# emojipad_v2.net
KiCad netlist of a schematic drawn in EAGLE
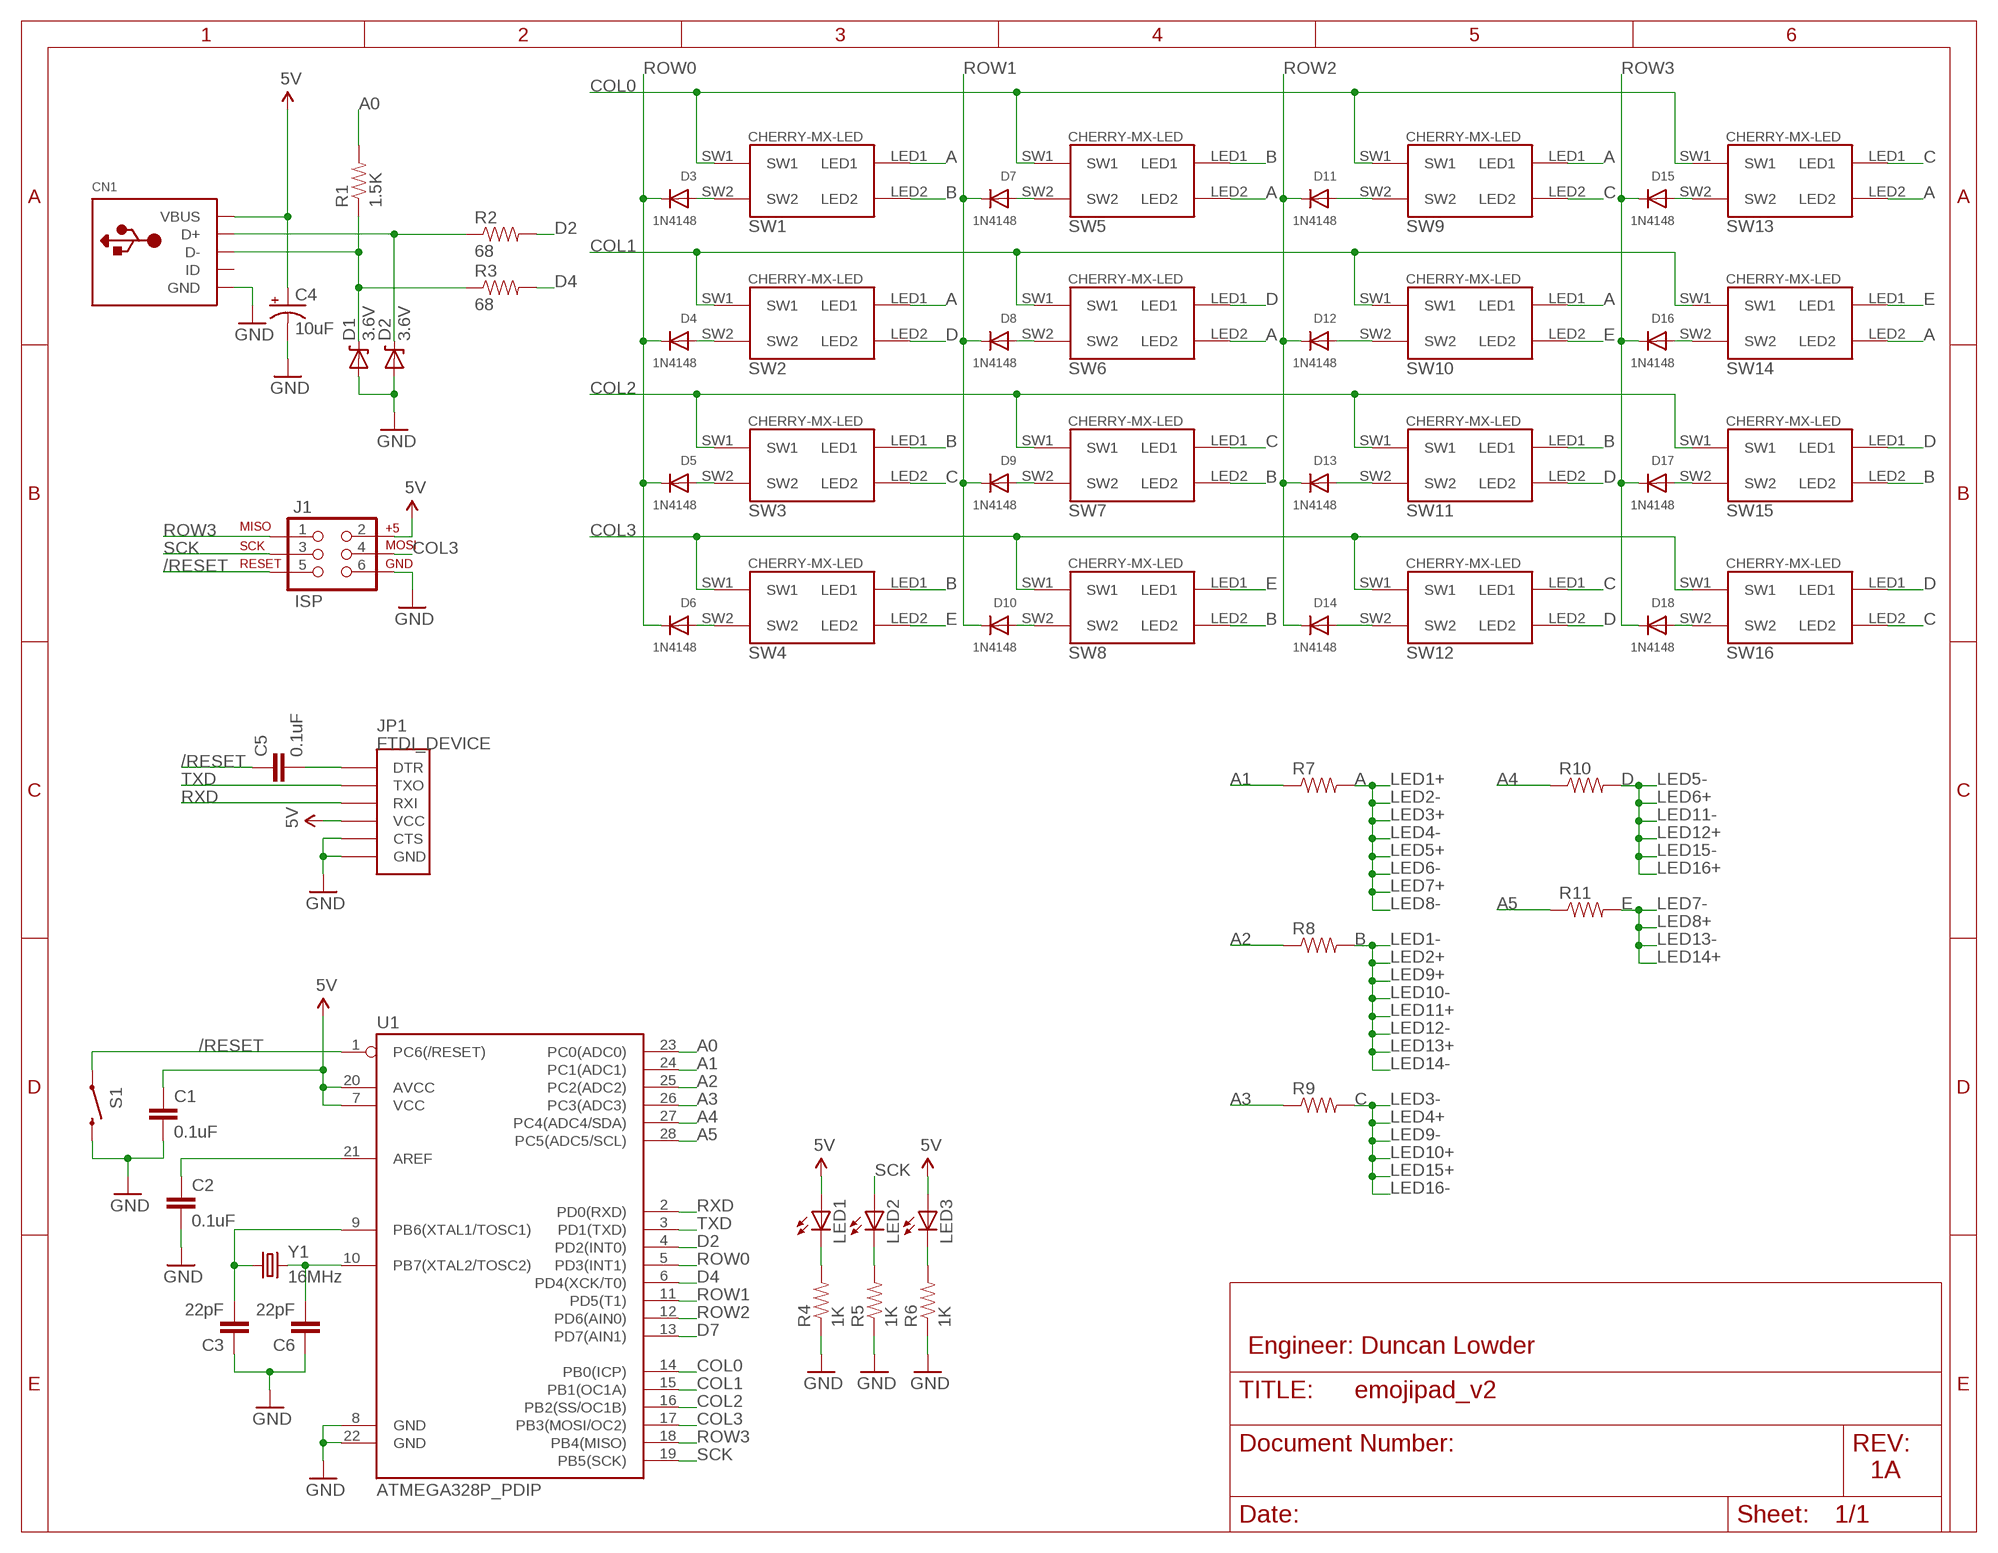
[diagram p0: schematic, sheet 1]

(export (version "E")
  (design (tool "Eeschema 10.0.6"))
  (components
    (comp (ref "C1")
      (value "0.1uF")
      (footprint "eagle-import:CAP-PTH-SMALL")
      (libsource (lib "eagle-import") (part "CAPPTH"))
    )
    (comp (ref "C2")
      (value "0.1uF")
      (footprint "eagle-import:CAP-PTH-SMALL")
      (libsource (lib "eagle-import") (part "CAPPTH"))
    )
    (comp (ref "C3")
      (value "22pF")
      (footprint "eagle-import:CAP-PTH-SMALL")
      (libsource (lib "eagle-import") (part "CAPPTH"))
    )
    (comp (ref "C4")
      (value "10uF")
      (footprint "eagle-import:CPOL-RADIAL-10UF-25V")
      (libsource (lib "eagle-import") (part "CAP_POLPTH2"))
    )
    (comp (ref "C5")
      (value "0.1uF")
      (footprint "eagle-import:CAP-PTH-SMALL")
      (libsource (lib "eagle-import") (part "SparkFun-Passives_CAPPTH"))
    )
    (comp (ref "C6")
      (value "22pF")
      (footprint "eagle-import:CAP-PTH-SMALL")
      (libsource (lib "eagle-import") (part "CAPPTH"))
    )
    (comp (ref "CN1")
      (value "USBMOLEX")
      (footprint "eagle-import:USB-MINIB-THM-MOLEX")
      (libsource (lib "eagle-import") (part "USBMOLEX"))
    )
    (comp (ref "D1")
      (value "3.6V")
      (footprint "eagle-import:DIODE-ZENER")
      (libsource (lib "eagle-import") (part "DIODE-ZENERPTH"))
    )
    (comp (ref "D2")
      (value "3.6V")
      (footprint "eagle-import:DIODE-ZENER")
      (libsource (lib "eagle-import") (part "DIODE-ZENERPTH"))
    )
    (comp (ref "D3")
      (value "1N4148")
      (footprint "eagle-import:DO-1N4148")
      (libsource (lib "eagle-import") (part "DIODEDO-1N4148"))
    )
    (comp (ref "D4")
      (value "1N4148")
      (footprint "eagle-import:DO-1N4148")
      (libsource (lib "eagle-import") (part "DIODEDO-1N4148"))
    )
    (comp (ref "D5")
      (value "1N4148")
      (footprint "eagle-import:DO-1N4148")
      (libsource (lib "eagle-import") (part "DIODEDO-1N4148"))
    )
    (comp (ref "D6")
      (value "1N4148")
      (footprint "eagle-import:DO-1N4148")
      (libsource (lib "eagle-import") (part "DIODEDO-1N4148"))
    )
    (comp (ref "D7")
      (value "1N4148")
      (footprint "eagle-import:DO-1N4148")
      (libsource (lib "eagle-import") (part "DIODEDO-1N4148"))
    )
    (comp (ref "D8")
      (value "1N4148")
      (footprint "eagle-import:DO-1N4148")
      (libsource (lib "eagle-import") (part "DIODEDO-1N4148"))
    )
    (comp (ref "D9")
      (value "1N4148")
      (footprint "eagle-import:DO-1N4148")
      (libsource (lib "eagle-import") (part "DIODEDO-1N4148"))
    )
    (comp (ref "D10")
      (value "1N4148")
      (footprint "eagle-import:DO-1N4148")
      (libsource (lib "eagle-import") (part "DIODEDO-1N4148"))
    )
    (comp (ref "D11")
      (value "1N4148")
      (footprint "eagle-import:DO-1N4148")
      (libsource (lib "eagle-import") (part "DIODEDO-1N4148"))
    )
    (comp (ref "D12")
      (value "1N4148")
      (footprint "eagle-import:DO-1N4148")
      (libsource (lib "eagle-import") (part "DIODEDO-1N4148"))
    )
    (comp (ref "D13")
      (value "1N4148")
      (footprint "eagle-import:DO-1N4148")
      (libsource (lib "eagle-import") (part "DIODEDO-1N4148"))
    )
    (comp (ref "D14")
      (value "1N4148")
      (footprint "eagle-import:DO-1N4148")
      (libsource (lib "eagle-import") (part "DIODEDO-1N4148"))
    )
    (comp (ref "D15")
      (value "1N4148")
      (footprint "eagle-import:DO-1N4148")
      (libsource (lib "eagle-import") (part "DIODEDO-1N4148"))
    )
    (comp (ref "D16")
      (value "1N4148")
      (footprint "eagle-import:DO-1N4148")
      (libsource (lib "eagle-import") (part "DIODEDO-1N4148"))
    )
    (comp (ref "D17")
      (value "1N4148")
      (footprint "eagle-import:DO-1N4148")
      (libsource (lib "eagle-import") (part "DIODEDO-1N4148"))
    )
    (comp (ref "D18")
      (value "1N4148")
      (footprint "eagle-import:DO-1N4148")
      (libsource (lib "eagle-import") (part "DIODEDO-1N4148"))
    )
    (comp (ref "J1")
      (value "ISP")
      (footprint "eagle-import:2X3")
      (libsource (lib "eagle-import") (part "AVR_SPI_PRG_6PTH"))
    )
    (comp (ref "JP1")
      (value "FTDI_DEVICE")
      (footprint "eagle-import:FTDI_DEVICE_SIDE")
      (libsource (lib "eagle-import") (part "FTDI_DEVICE"))
    )
    (comp (ref "LED1")
      (value "LED3MM")
      (footprint "eagle-import:LED3MM")
      (libsource (lib "eagle-import") (part "LED3MM"))
    )
    (comp (ref "LED2")
      (value "LED3MM")
      (footprint "eagle-import:LED3MM")
      (libsource (lib "eagle-import") (part "LED3MM"))
    )
    (comp (ref "LED3")
      (value "LED3MM")
      (footprint "eagle-import:LED3MM")
      (libsource (lib "eagle-import") (part "LED3MM"))
    )
    (comp (ref "R1")
      (value "1.5K")
      (footprint "eagle-import:AXIAL-0.3")
      (libsource (lib "eagle-import") (part "RESISTORAXIAL-0.3"))
    )
    (comp (ref "R2")
      (value "68")
      (footprint "eagle-import:AXIAL-0.3")
      (libsource (lib "eagle-import") (part "SparkFun-Resistors_RESISTORAXIAL-0.3"))
    )
    (comp (ref "R3")
      (value "68")
      (footprint "eagle-import:AXIAL-0.3")
      (libsource (lib "eagle-import") (part "SparkFun-Resistors_RESISTORAXIAL-0.3"))
    )
    (comp (ref "R4")
      (value "1K")
      (footprint "eagle-import:AXIAL-0.3")
      (libsource (lib "eagle-import") (part "RESISTORAXIAL-0.3"))
    )
    (comp (ref "R5")
      (value "1K")
      (footprint "eagle-import:AXIAL-0.3")
      (libsource (lib "eagle-import") (part "RESISTORAXIAL-0.3"))
    )
    (comp (ref "R6")
      (value "1K")
      (footprint "eagle-import:AXIAL-0.3")
      (libsource (lib "eagle-import") (part "RESISTORAXIAL-0.3"))
    )
    (comp (ref "R7")
      (value "RESISTORAXIAL-0.3")
      (footprint "eagle-import:AXIAL-0.3")
      (libsource (lib "eagle-import") (part "RESISTORAXIAL-0.3"))
    )
    (comp (ref "R8")
      (value "RESISTORAXIAL-0.3")
      (footprint "eagle-import:AXIAL-0.3")
      (libsource (lib "eagle-import") (part "RESISTORAXIAL-0.3"))
    )
    (comp (ref "R9")
      (value "RESISTORAXIAL-0.3")
      (footprint "eagle-import:AXIAL-0.3")
      (libsource (lib "eagle-import") (part "RESISTORAXIAL-0.3"))
    )
    (comp (ref "R10")
      (value "RESISTORAXIAL-0.3")
      (footprint "eagle-import:AXIAL-0.3")
      (libsource (lib "eagle-import") (part "RESISTORAXIAL-0.3"))
    )
    (comp (ref "R11")
      (value "RESISTORAXIAL-0.3")
      (footprint "eagle-import:AXIAL-0.3")
      (libsource (lib "eagle-import") (part "RESISTORAXIAL-0.3"))
    )
    (comp (ref "S1")
      (value "SWITCH-MOMENTARY-2SIDE_EZ")
      (footprint "eagle-import:TACTILE-PTH-SIDEEZ")
      (libsource (lib "eagle-import") (part "SWITCH-MOMENTARY-2SIDE_EZ"))
    )
    (comp (ref "SW1")
      (value "CHERRY-MX-LED")
      (footprint "eagle-import:CHERRY-MX-LED")
      (libsource (lib "eagle-import") (part "CHERRY-MX-LED"))
    )
    (comp (ref "SW2")
      (value "CHERRY-MX-LED")
      (footprint "eagle-import:CHERRY-MX-LED")
      (libsource (lib "eagle-import") (part "CHERRY-MX-LED"))
    )
    (comp (ref "SW3")
      (value "CHERRY-MX-LED")
      (footprint "eagle-import:CHERRY-MX-LED")
      (libsource (lib "eagle-import") (part "CHERRY-MX-LED"))
    )
    (comp (ref "SW4")
      (value "CHERRY-MX-LED")
      (footprint "eagle-import:CHERRY-MX-LED")
      (libsource (lib "eagle-import") (part "CHERRY-MX-LED"))
    )
    (comp (ref "SW5")
      (value "CHERRY-MX-LED")
      (footprint "eagle-import:CHERRY-MX-LED")
      (libsource (lib "eagle-import") (part "CHERRY-MX-LED"))
    )
    (comp (ref "SW6")
      (value "CHERRY-MX-LED")
      (footprint "eagle-import:CHERRY-MX-LED")
      (libsource (lib "eagle-import") (part "CHERRY-MX-LED"))
    )
    (comp (ref "SW7")
      (value "CHERRY-MX-LED")
      (footprint "eagle-import:CHERRY-MX-LED")
      (libsource (lib "eagle-import") (part "CHERRY-MX-LED"))
    )
    (comp (ref "SW8")
      (value "CHERRY-MX-LED")
      (footprint "eagle-import:CHERRY-MX-LED")
      (libsource (lib "eagle-import") (part "CHERRY-MX-LED"))
    )
    (comp (ref "SW9")
      (value "CHERRY-MX-LED")
      (footprint "eagle-import:CHERRY-MX-LED")
      (libsource (lib "eagle-import") (part "CHERRY-MX-LED"))
    )
    (comp (ref "SW10")
      (value "CHERRY-MX-LED")
      (footprint "eagle-import:CHERRY-MX-LED")
      (libsource (lib "eagle-import") (part "CHERRY-MX-LED"))
    )
    (comp (ref "SW11")
      (value "CHERRY-MX-LED")
      (footprint "eagle-import:CHERRY-MX-LED")
      (libsource (lib "eagle-import") (part "CHERRY-MX-LED"))
    )
    (comp (ref "SW12")
      (value "CHERRY-MX-LED")
      (footprint "eagle-import:CHERRY-MX-LED")
      (libsource (lib "eagle-import") (part "CHERRY-MX-LED"))
    )
    (comp (ref "SW13")
      (value "CHERRY-MX-LED")
      (footprint "eagle-import:CHERRY-MX-LED")
      (libsource (lib "eagle-import") (part "CHERRY-MX-LED"))
    )
    (comp (ref "SW14")
      (value "CHERRY-MX-LED")
      (footprint "eagle-import:CHERRY-MX-LED")
      (libsource (lib "eagle-import") (part "CHERRY-MX-LED"))
    )
    (comp (ref "SW15")
      (value "CHERRY-MX-LED")
      (footprint "eagle-import:CHERRY-MX-LED")
      (libsource (lib "eagle-import") (part "CHERRY-MX-LED"))
    )
    (comp (ref "SW16")
      (value "CHERRY-MX-LED")
      (footprint "eagle-import:CHERRY-MX-LED")
      (libsource (lib "eagle-import") (part "CHERRY-MX-LED"))
    )
    (comp (ref "U1")
      (value "ATMEGA328P_PDIP")
      (footprint "eagle-import:DIL28-3")
      (libsource (lib "eagle-import") (part "ATMEGA328P_PDIP"))
    )
    (comp (ref "Y1")
      (value "16MHz")
      (footprint "eagle-import:HC49US")
      (libsource (lib "eagle-import") (part "CRYSTALHC49US"))
    )
  )
  (nets
    (net (code "1") (name "/A") (class "Default")
      (node (ref "R7") (pin "P$2") (pinfunction "2_P$2") (pintype "passive"))
      (node (ref "SW1") (pin "LED1") (pinfunction "LED1_LED1") (pintype "bidirectional"))
      (node (ref "SW10") (pin "LED1") (pinfunction "LED1_LED1") (pintype "bidirectional"))
      (node (ref "SW13") (pin "LED2") (pinfunction "LED2_LED2") (pintype "bidirectional"))
      (node (ref "SW14") (pin "LED2") (pinfunction "LED2_LED2") (pintype "bidirectional"))
      (node (ref "SW2") (pin "LED1") (pinfunction "LED1_LED1") (pintype "bidirectional"))
      (node (ref "SW5") (pin "LED2") (pinfunction "LED2_LED2") (pintype "bidirectional"))
      (node (ref "SW6") (pin "LED2") (pinfunction "LED2_LED2") (pintype "bidirectional"))
      (node (ref "SW9") (pin "LED1") (pinfunction "LED1_LED1") (pintype "bidirectional"))
    )
    (net (code "2") (name "/A0") (class "Default")
      (node (ref "R1") (pin "P$2") (pinfunction "2_P$2") (pintype "passive"))
      (node (ref "U1") (pin "23") (pinfunction "PC0(ADC0)_23") (pintype "bidirectional"))
    )
    (net (code "3") (name "/A1") (class "Default")
      (node (ref "R7") (pin "P$1") (pinfunction "1_P$1") (pintype "passive"))
      (node (ref "U1") (pin "24") (pinfunction "PC1(ADC1)_24") (pintype "bidirectional"))
    )
    (net (code "4") (name "/A2") (class "Default")
      (node (ref "R8") (pin "P$1") (pinfunction "1_P$1") (pintype "passive"))
      (node (ref "U1") (pin "25") (pinfunction "PC2(ADC2)_25") (pintype "bidirectional"))
    )
    (net (code "5") (name "/A3") (class "Default")
      (node (ref "R9") (pin "P$1") (pinfunction "1_P$1") (pintype "passive"))
      (node (ref "U1") (pin "26") (pinfunction "PC3(ADC3)_26") (pintype "bidirectional"))
    )
    (net (code "6") (name "/A4") (class "Default")
      (node (ref "R10") (pin "P$1") (pinfunction "1_P$1") (pintype "passive"))
      (node (ref "U1") (pin "27") (pinfunction "PC4(ADC4/SDA)_27") (pintype "bidirectional"))
    )
    (net (code "7") (name "/A5") (class "Default")
      (node (ref "R11") (pin "P$1") (pinfunction "1_P$1") (pintype "passive"))
      (node (ref "U1") (pin "28") (pinfunction "PC5(ADC5/SCL)_28") (pintype "bidirectional"))
    )
    (net (code "8") (name "/B") (class "Default")
      (node (ref "R8") (pin "P$2") (pinfunction "2_P$2") (pintype "passive"))
      (node (ref "SW1") (pin "LED2") (pinfunction "LED2_LED2") (pintype "bidirectional"))
      (node (ref "SW11") (pin "LED1") (pinfunction "LED1_LED1") (pintype "bidirectional"))
      (node (ref "SW15") (pin "LED2") (pinfunction "LED2_LED2") (pintype "bidirectional"))
      (node (ref "SW3") (pin "LED1") (pinfunction "LED1_LED1") (pintype "bidirectional"))
      (node (ref "SW4") (pin "LED1") (pinfunction "LED1_LED1") (pintype "bidirectional"))
      (node (ref "SW5") (pin "LED1") (pinfunction "LED1_LED1") (pintype "bidirectional"))
      (node (ref "SW7") (pin "LED2") (pinfunction "LED2_LED2") (pintype "bidirectional"))
      (node (ref "SW8") (pin "LED2") (pinfunction "LED2_LED2") (pintype "bidirectional"))
    )
    (net (code "9") (name "/C") (class "Default")
      (node (ref "R9") (pin "P$2") (pinfunction "2_P$2") (pintype "passive"))
      (node (ref "SW12") (pin "LED1") (pinfunction "LED1_LED1") (pintype "bidirectional"))
      (node (ref "SW13") (pin "LED1") (pinfunction "LED1_LED1") (pintype "bidirectional"))
      (node (ref "SW16") (pin "LED2") (pinfunction "LED2_LED2") (pintype "bidirectional"))
      (node (ref "SW3") (pin "LED2") (pinfunction "LED2_LED2") (pintype "bidirectional"))
      (node (ref "SW7") (pin "LED1") (pinfunction "LED1_LED1") (pintype "bidirectional"))
      (node (ref "SW9") (pin "LED2") (pinfunction "LED2_LED2") (pintype "bidirectional"))
    )
    (net (code "10") (name "/COL0") (class "Default")
      (node (ref "SW1") (pin "SW1") (pinfunction "SW1_SW1") (pintype "bidirectional"))
      (node (ref "SW13") (pin "SW1") (pinfunction "SW1_SW1") (pintype "bidirectional"))
      (node (ref "SW5") (pin "SW1") (pinfunction "SW1_SW1") (pintype "bidirectional"))
      (node (ref "SW9") (pin "SW1") (pinfunction "SW1_SW1") (pintype "bidirectional"))
      (node (ref "U1") (pin "14") (pinfunction "PB0(ICP)_14") (pintype "bidirectional"))
    )
    (net (code "11") (name "/COL1") (class "Default")
      (node (ref "SW10") (pin "SW1") (pinfunction "SW1_SW1") (pintype "bidirectional"))
      (node (ref "SW14") (pin "SW1") (pinfunction "SW1_SW1") (pintype "bidirectional"))
      (node (ref "SW2") (pin "SW1") (pinfunction "SW1_SW1") (pintype "bidirectional"))
      (node (ref "SW6") (pin "SW1") (pinfunction "SW1_SW1") (pintype "bidirectional"))
      (node (ref "U1") (pin "15") (pinfunction "PB1(OC1A)_15") (pintype "bidirectional"))
    )
    (net (code "12") (name "/COL2") (class "Default")
      (node (ref "SW11") (pin "SW1") (pinfunction "SW1_SW1") (pintype "bidirectional"))
      (node (ref "SW15") (pin "SW1") (pinfunction "SW1_SW1") (pintype "bidirectional"))
      (node (ref "SW3") (pin "SW1") (pinfunction "SW1_SW1") (pintype "bidirectional"))
      (node (ref "SW7") (pin "SW1") (pinfunction "SW1_SW1") (pintype "bidirectional"))
      (node (ref "U1") (pin "16") (pinfunction "PB2(SS/OC1B)_16") (pintype "bidirectional"))
    )
    (net (code "13") (name "/COL3") (class "Default")
      (node (ref "J1") (pin "4") (pinfunction "4_4") (pintype "passive"))
      (node (ref "SW12") (pin "SW1") (pinfunction "SW1_SW1") (pintype "bidirectional"))
      (node (ref "SW16") (pin "SW1") (pinfunction "SW1_SW1") (pintype "bidirectional"))
      (node (ref "SW4") (pin "SW1") (pinfunction "SW1_SW1") (pintype "bidirectional"))
      (node (ref "SW8") (pin "SW1") (pinfunction "SW1_SW1") (pintype "bidirectional"))
      (node (ref "U1") (pin "17") (pinfunction "PB3(MOSI/OC2)_17") (pintype "bidirectional"))
    )
    (net (code "14") (name "/D") (class "Default")
      (node (ref "R10") (pin "P$2") (pinfunction "2_P$2") (pintype "passive"))
      (node (ref "SW11") (pin "LED2") (pinfunction "LED2_LED2") (pintype "bidirectional"))
      (node (ref "SW12") (pin "LED2") (pinfunction "LED2_LED2") (pintype "bidirectional"))
      (node (ref "SW15") (pin "LED1") (pinfunction "LED1_LED1") (pintype "bidirectional"))
      (node (ref "SW16") (pin "LED1") (pinfunction "LED1_LED1") (pintype "bidirectional"))
      (node (ref "SW2") (pin "LED2") (pinfunction "LED2_LED2") (pintype "bidirectional"))
      (node (ref "SW6") (pin "LED1") (pinfunction "LED1_LED1") (pintype "bidirectional"))
    )
    (net (code "15") (name "/D2") (class "Default")
      (node (ref "R2") (pin "P$2") (pinfunction "2_P$2") (pintype "passive"))
      (node (ref "U1") (pin "4") (pinfunction "PD2(INT0)_4") (pintype "bidirectional"))
    )
    (net (code "16") (name "/D4") (class "Default")
      (node (ref "R3") (pin "P$2") (pinfunction "2_P$2") (pintype "passive"))
      (node (ref "U1") (pin "6") (pinfunction "PD4(XCK/T0)_6") (pintype "bidirectional"))
    )
    (net (code "17") (name "/D7") (class "Default")
      (node (ref "U1") (pin "13") (pinfunction "PD7(AIN1)_13") (pintype "bidirectional"))
    )
    (net (code "18") (name "/E") (class "Default")
      (node (ref "R11") (pin "P$2") (pinfunction "2_P$2") (pintype "passive"))
      (node (ref "SW10") (pin "LED2") (pinfunction "LED2_LED2") (pintype "bidirectional"))
      (node (ref "SW14") (pin "LED1") (pinfunction "LED1_LED1") (pintype "bidirectional"))
      (node (ref "SW4") (pin "LED2") (pinfunction "LED2_LED2") (pintype "bidirectional"))
      (node (ref "SW8") (pin "LED1") (pinfunction "LED1_LED1") (pintype "bidirectional"))
    )
    (net (code "19") (name "/ROW0") (class "Default")
      (node (ref "D3") (pin "C") (pinfunction "C_C") (pintype "passive"))
      (node (ref "D4") (pin "C") (pinfunction "C_C") (pintype "passive"))
      (node (ref "D5") (pin "C") (pinfunction "C_C") (pintype "passive"))
      (node (ref "D6") (pin "C") (pinfunction "C_C") (pintype "passive"))
      (node (ref "U1") (pin "5") (pinfunction "PD3(INT1)_5") (pintype "bidirectional"))
    )
    (net (code "20") (name "/ROW1") (class "Default")
      (node (ref "D10") (pin "C") (pinfunction "C_C") (pintype "passive"))
      (node (ref "D7") (pin "C") (pinfunction "C_C") (pintype "passive"))
      (node (ref "D8") (pin "C") (pinfunction "C_C") (pintype "passive"))
      (node (ref "D9") (pin "C") (pinfunction "C_C") (pintype "passive"))
      (node (ref "U1") (pin "11") (pinfunction "PD5(T1)_11") (pintype "bidirectional"))
    )
    (net (code "21") (name "/ROW2") (class "Default")
      (node (ref "D11") (pin "C") (pinfunction "C_C") (pintype "passive"))
      (node (ref "D12") (pin "C") (pinfunction "C_C") (pintype "passive"))
      (node (ref "D13") (pin "C") (pinfunction "C_C") (pintype "passive"))
      (node (ref "D14") (pin "C") (pinfunction "C_C") (pintype "passive"))
      (node (ref "U1") (pin "12") (pinfunction "PD6(AIN0)_12") (pintype "bidirectional"))
    )
    (net (code "22") (name "/ROW3") (class "Default")
      (node (ref "D15") (pin "C") (pinfunction "C_C") (pintype "passive"))
      (node (ref "D16") (pin "C") (pinfunction "C_C") (pintype "passive"))
      (node (ref "D17") (pin "C") (pinfunction "C_C") (pintype "passive"))
      (node (ref "D18") (pin "C") (pinfunction "C_C") (pintype "passive"))
      (node (ref "J1") (pin "1") (pinfunction "1_1") (pintype "passive"))
      (node (ref "U1") (pin "18") (pinfunction "PB4(MISO)_18") (pintype "bidirectional"))
    )
    (net (code "23") (name "/RXD") (class "Default")
      (node (ref "JP1") (pin "P$3") (pinfunction "RXI_P$3") (pintype "bidirectional"))
      (node (ref "U1") (pin "2") (pinfunction "PD0(RXD)_2") (pintype "bidirectional"))
    )
    (net (code "24") (name "/SCK") (class "Default")
      (node (ref "J1") (pin "3") (pinfunction "3_3") (pintype "passive"))
      (node (ref "LED2") (pin "A") (pinfunction "A_A") (pintype "passive"))
      (node (ref "U1") (pin "19") (pinfunction "PB5(SCK)_19") (pintype "bidirectional"))
    )
    (net (code "25") (name "/TXD") (class "Default")
      (node (ref "JP1") (pin "P$2") (pinfunction "TXO_P$2") (pintype "bidirectional"))
      (node (ref "U1") (pin "3") (pinfunction "PD1(TXD)_3") (pintype "bidirectional"))
    )
    (net (code "26") (name "/{slash}RESET") (class "Default")
      (node (ref "C5") (pin "1") (pinfunction "1_1") (pintype "passive"))
      (node (ref "J1") (pin "5") (pinfunction "5_5") (pintype "passive"))
      (node (ref "S1") (pin "1") (pinfunction "1_1") (pintype "passive"))
      (node (ref "U1") (pin "1") (pinfunction "PC6(/RESET)_1") (pintype "bidirectional"))
    )
    (net (code "27") (name "5V") (class "Default")
      (node (ref "C1") (pin "1") (pinfunction "1_1") (pintype "passive"))
      (node (ref "C4") (pin "1") (pinfunction "+_1") (pintype "passive"))
      (node (ref "CN1") (pin "VBUS") (pinfunction "VBUS_VBUS") (pintype "power_in"))
      (node (ref "J1") (pin "2") (pinfunction "2_2") (pintype "passive"))
      (node (ref "JP1") (pin "P$4") (pinfunction "VCC_P$4") (pintype "bidirectional"))
      (node (ref "LED1") (pin "A") (pinfunction "A_A") (pintype "passive"))
      (node (ref "LED3") (pin "A") (pinfunction "A_A") (pintype "passive"))
      (node (ref "U1") (pin "20") (pinfunction "AVCC_20") (pintype "bidirectional"))
      (node (ref "U1") (pin "7") (pinfunction "VCC_7") (pintype "bidirectional"))
    )
    (net (code "28") (name "GND") (class "Default")
      (node (ref "C1") (pin "2") (pinfunction "2_2") (pintype "passive"))
      (node (ref "C2") (pin "2") (pinfunction "2_2") (pintype "passive"))
      (node (ref "C3") (pin "1") (pinfunction "1_1") (pintype "passive"))
      (node (ref "C4") (pin "2") (pinfunction "-_2") (pintype "passive"))
      (node (ref "C6") (pin "1") (pinfunction "1_1") (pintype "passive"))
      (node (ref "CN1") (pin "GND") (pinfunction "GND_GND") (pintype "power_in"))
      (node (ref "D1") (pin "P$2") (pinfunction "A_P$2") (pintype "passive"))
      (node (ref "D2") (pin "P$2") (pinfunction "A_P$2") (pintype "passive"))
      (node (ref "J1") (pin "6") (pinfunction "6_6") (pintype "passive"))
      (node (ref "JP1") (pin "P$5") (pinfunction "CTS_P$5") (pintype "bidirectional"))
      (node (ref "JP1") (pin "P$6") (pinfunction "GND_P$6") (pintype "bidirectional"))
      (node (ref "R4") (pin "P$1") (pinfunction "1_P$1") (pintype "passive"))
      (node (ref "R5") (pin "P$1") (pinfunction "1_P$1") (pintype "passive"))
      (node (ref "R6") (pin "P$1") (pinfunction "1_P$1") (pintype "passive"))
      (node (ref "S1") (pin "2") (pinfunction "2_2") (pintype "passive"))
      (node (ref "U1") (pin "22") (pinfunction "GND_22") (pintype "bidirectional"))
      (node (ref "U1") (pin "8") (pinfunction "GND_8") (pintype "bidirectional"))
    )
    (net (code "29") (name "Net-(D1-C)") (class "Default")
      (node (ref "CN1") (pin "D-") (pinfunction "D-_D-") (pintype "bidirectional"))
      (node (ref "D1") (pin "P$1") (pinfunction "C_P$1") (pintype "passive"))
      (node (ref "R1") (pin "P$1") (pinfunction "1_P$1") (pintype "passive"))
      (node (ref "R3") (pin "P$1") (pinfunction "1_P$1") (pintype "passive"))
    )
    (net (code "30") (name "Net-(D2-C)") (class "Default")
      (node (ref "CN1") (pin "D+") (pinfunction "D+_D+") (pintype "bidirectional"))
      (node (ref "D2") (pin "P$1") (pinfunction "C_P$1") (pintype "passive"))
      (node (ref "R2") (pin "P$1") (pinfunction "1_P$1") (pintype "passive"))
    )
    (net (code "31") (name "Net-(D3-PadA)") (class "Default")
      (node (ref "D3") (pin "A") (pinfunction "A_A") (pintype "passive"))
      (node (ref "SW1") (pin "SW2") (pinfunction "SW2_SW2") (pintype "bidirectional"))
    )
    (net (code "32") (name "Net-(D4-PadA)") (class "Default")
      (node (ref "D4") (pin "A") (pinfunction "A_A") (pintype "passive"))
      (node (ref "SW2") (pin "SW2") (pinfunction "SW2_SW2") (pintype "bidirectional"))
    )
    (net (code "33") (name "Net-(D5-PadA)") (class "Default")
      (node (ref "D5") (pin "A") (pinfunction "A_A") (pintype "passive"))
      (node (ref "SW3") (pin "SW2") (pinfunction "SW2_SW2") (pintype "bidirectional"))
    )
    (net (code "34") (name "Net-(D6-PadA)") (class "Default")
      (node (ref "D6") (pin "A") (pinfunction "A_A") (pintype "passive"))
      (node (ref "SW4") (pin "SW2") (pinfunction "SW2_SW2") (pintype "bidirectional"))
    )
    (net (code "35") (name "Net-(D7-PadA)") (class "Default")
      (node (ref "D7") (pin "A") (pinfunction "A_A") (pintype "passive"))
      (node (ref "SW5") (pin "SW2") (pinfunction "SW2_SW2") (pintype "bidirectional"))
    )
    (net (code "36") (name "Net-(D8-PadA)") (class "Default")
      (node (ref "D8") (pin "A") (pinfunction "A_A") (pintype "passive"))
      (node (ref "SW6") (pin "SW2") (pinfunction "SW2_SW2") (pintype "bidirectional"))
    )
    (net (code "37") (name "Net-(D9-PadA)") (class "Default")
      (node (ref "D9") (pin "A") (pinfunction "A_A") (pintype "passive"))
      (node (ref "SW7") (pin "SW2") (pinfunction "SW2_SW2") (pintype "bidirectional"))
    )
    (net (code "38") (name "Net-(D10-PadA)") (class "Default")
      (node (ref "D10") (pin "A") (pinfunction "A_A") (pintype "passive"))
      (node (ref "SW8") (pin "SW2") (pinfunction "SW2_SW2") (pintype "bidirectional"))
    )
    (net (code "39") (name "Net-(D11-PadA)") (class "Default")
      (node (ref "D11") (pin "A") (pinfunction "A_A") (pintype "passive"))
      (node (ref "SW9") (pin "SW2") (pinfunction "SW2_SW2") (pintype "bidirectional"))
    )
    (net (code "40") (name "Net-(D12-PadA)") (class "Default")
      (node (ref "D12") (pin "A") (pinfunction "A_A") (pintype "passive"))
      (node (ref "SW10") (pin "SW2") (pinfunction "SW2_SW2") (pintype "bidirectional"))
    )
    (net (code "41") (name "Net-(D13-PadA)") (class "Default")
      (node (ref "D13") (pin "A") (pinfunction "A_A") (pintype "passive"))
      (node (ref "SW11") (pin "SW2") (pinfunction "SW2_SW2") (pintype "bidirectional"))
    )
    (net (code "42") (name "Net-(D14-PadA)") (class "Default")
      (node (ref "D14") (pin "A") (pinfunction "A_A") (pintype "passive"))
      (node (ref "SW12") (pin "SW2") (pinfunction "SW2_SW2") (pintype "bidirectional"))
    )
    (net (code "43") (name "Net-(D15-PadA)") (class "Default")
      (node (ref "D15") (pin "A") (pinfunction "A_A") (pintype "passive"))
      (node (ref "SW13") (pin "SW2") (pinfunction "SW2_SW2") (pintype "bidirectional"))
    )
    (net (code "44") (name "Net-(D16-PadA)") (class "Default")
      (node (ref "D16") (pin "A") (pinfunction "A_A") (pintype "passive"))
      (node (ref "SW14") (pin "SW2") (pinfunction "SW2_SW2") (pintype "bidirectional"))
    )
    (net (code "45") (name "Net-(D17-PadA)") (class "Default")
      (node (ref "D17") (pin "A") (pinfunction "A_A") (pintype "passive"))
      (node (ref "SW15") (pin "SW2") (pinfunction "SW2_SW2") (pintype "bidirectional"))
    )
    (net (code "46") (name "Net-(D18-PadA)") (class "Default")
      (node (ref "D18") (pin "A") (pinfunction "A_A") (pintype "passive"))
      (node (ref "SW16") (pin "SW2") (pinfunction "SW2_SW2") (pintype "bidirectional"))
    )
    (net (code "47") (name "Net-(JP1-DTR)") (class "Default")
      (node (ref "C5") (pin "2") (pinfunction "2_2") (pintype "passive"))
      (node (ref "JP1") (pin "P$1") (pinfunction "DTR_P$1") (pintype "bidirectional"))
    )
    (net (code "48") (name "Net-(LED1-C)") (class "Default")
      (node (ref "LED1") (pin "K") (pinfunction "C_K") (pintype "passive"))
      (node (ref "R4") (pin "P$2") (pinfunction "2_P$2") (pintype "passive"))
    )
    (net (code "49") (name "Net-(LED2-C)") (class "Default")
      (node (ref "LED2") (pin "K") (pinfunction "C_K") (pintype "passive"))
      (node (ref "R5") (pin "P$2") (pinfunction "2_P$2") (pintype "passive"))
    )
    (net (code "50") (name "Net-(LED3-C)") (class "Default")
      (node (ref "LED3") (pin "K") (pinfunction "C_K") (pintype "passive"))
      (node (ref "R6") (pin "P$2") (pinfunction "2_P$2") (pintype "passive"))
    )
    (net (code "51") (name "Net-(U1-AREF)") (class "Default")
      (node (ref "C2") (pin "1") (pinfunction "1_1") (pintype "passive"))
      (node (ref "U1") (pin "21") (pinfunction "AREF_21") (pintype "bidirectional"))
    )
    (net (code "52") (name "Net-(U1-PB6(XTAL1{slash}TOSC1))") (class "Default")
      (node (ref "C3") (pin "2") (pinfunction "2_2") (pintype "passive"))
      (node (ref "U1") (pin "9") (pinfunction "PB6(XTAL1/TOSC1)_9") (pintype "bidirectional"))
      (node (ref "Y1") (pin "1") (pinfunction "1_1") (pintype "passive"))
    )
    (net (code "53") (name "Net-(U1-PB7(XTAL2{slash}TOSC2))") (class "Default")
      (node (ref "C6") (pin "2") (pinfunction "2_2") (pintype "passive"))
      (node (ref "U1") (pin "10") (pinfunction "PB7(XTAL2/TOSC2)_10") (pintype "bidirectional"))
      (node (ref "Y1") (pin "2") (pinfunction "2_2") (pintype "passive"))
    )
    (net (code "54") (name "unconnected-(CN1-PadID)") (class "Default")
      (node (ref "CN1") (pin "ID") (pinfunction "ID_ID") (pintype "bidirectional"))
    )
  )
)
